# development_board.net
KiCad netlist of a schematic drawn in EAGLE
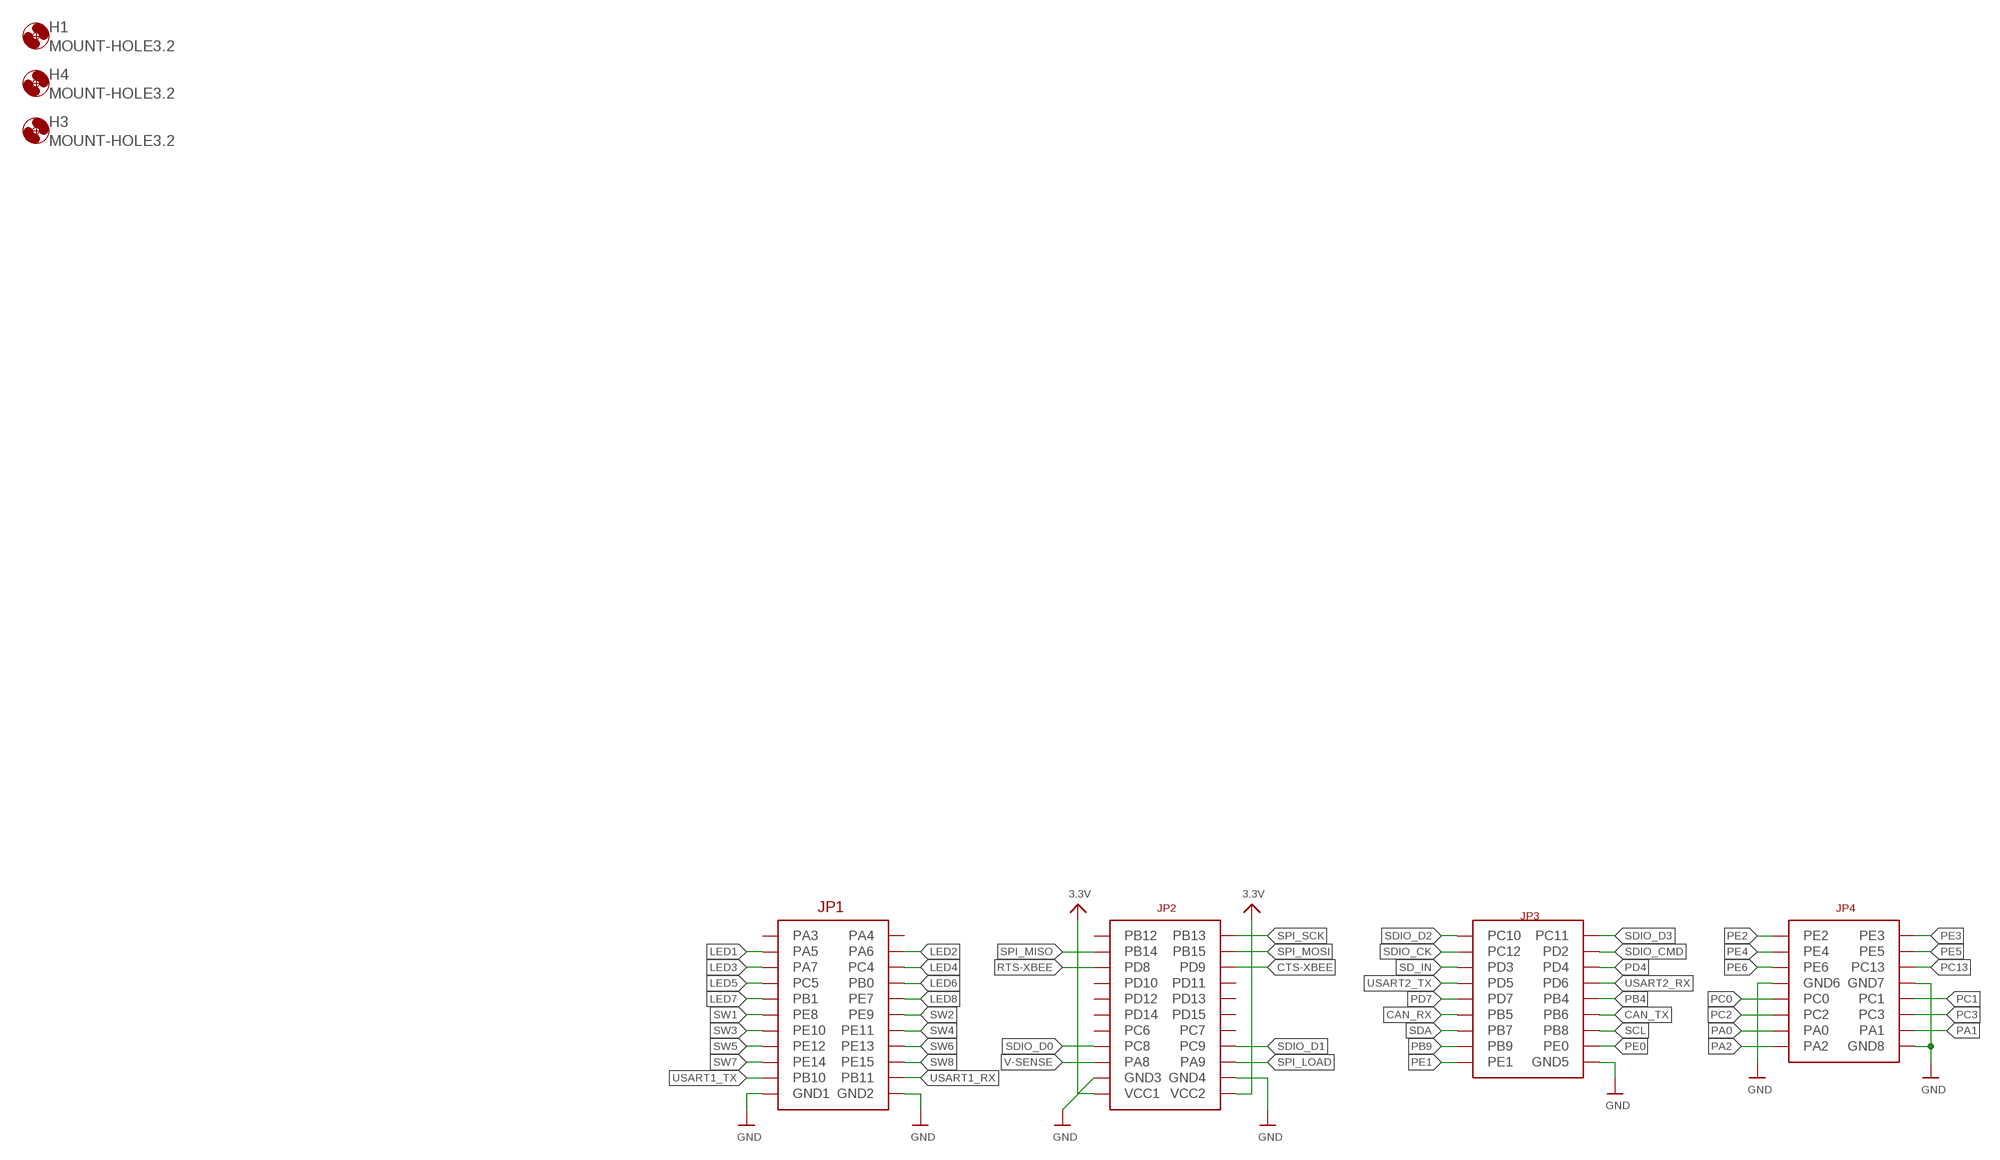
[diagram p0: schematic, sheet 1, part 1 of 3]
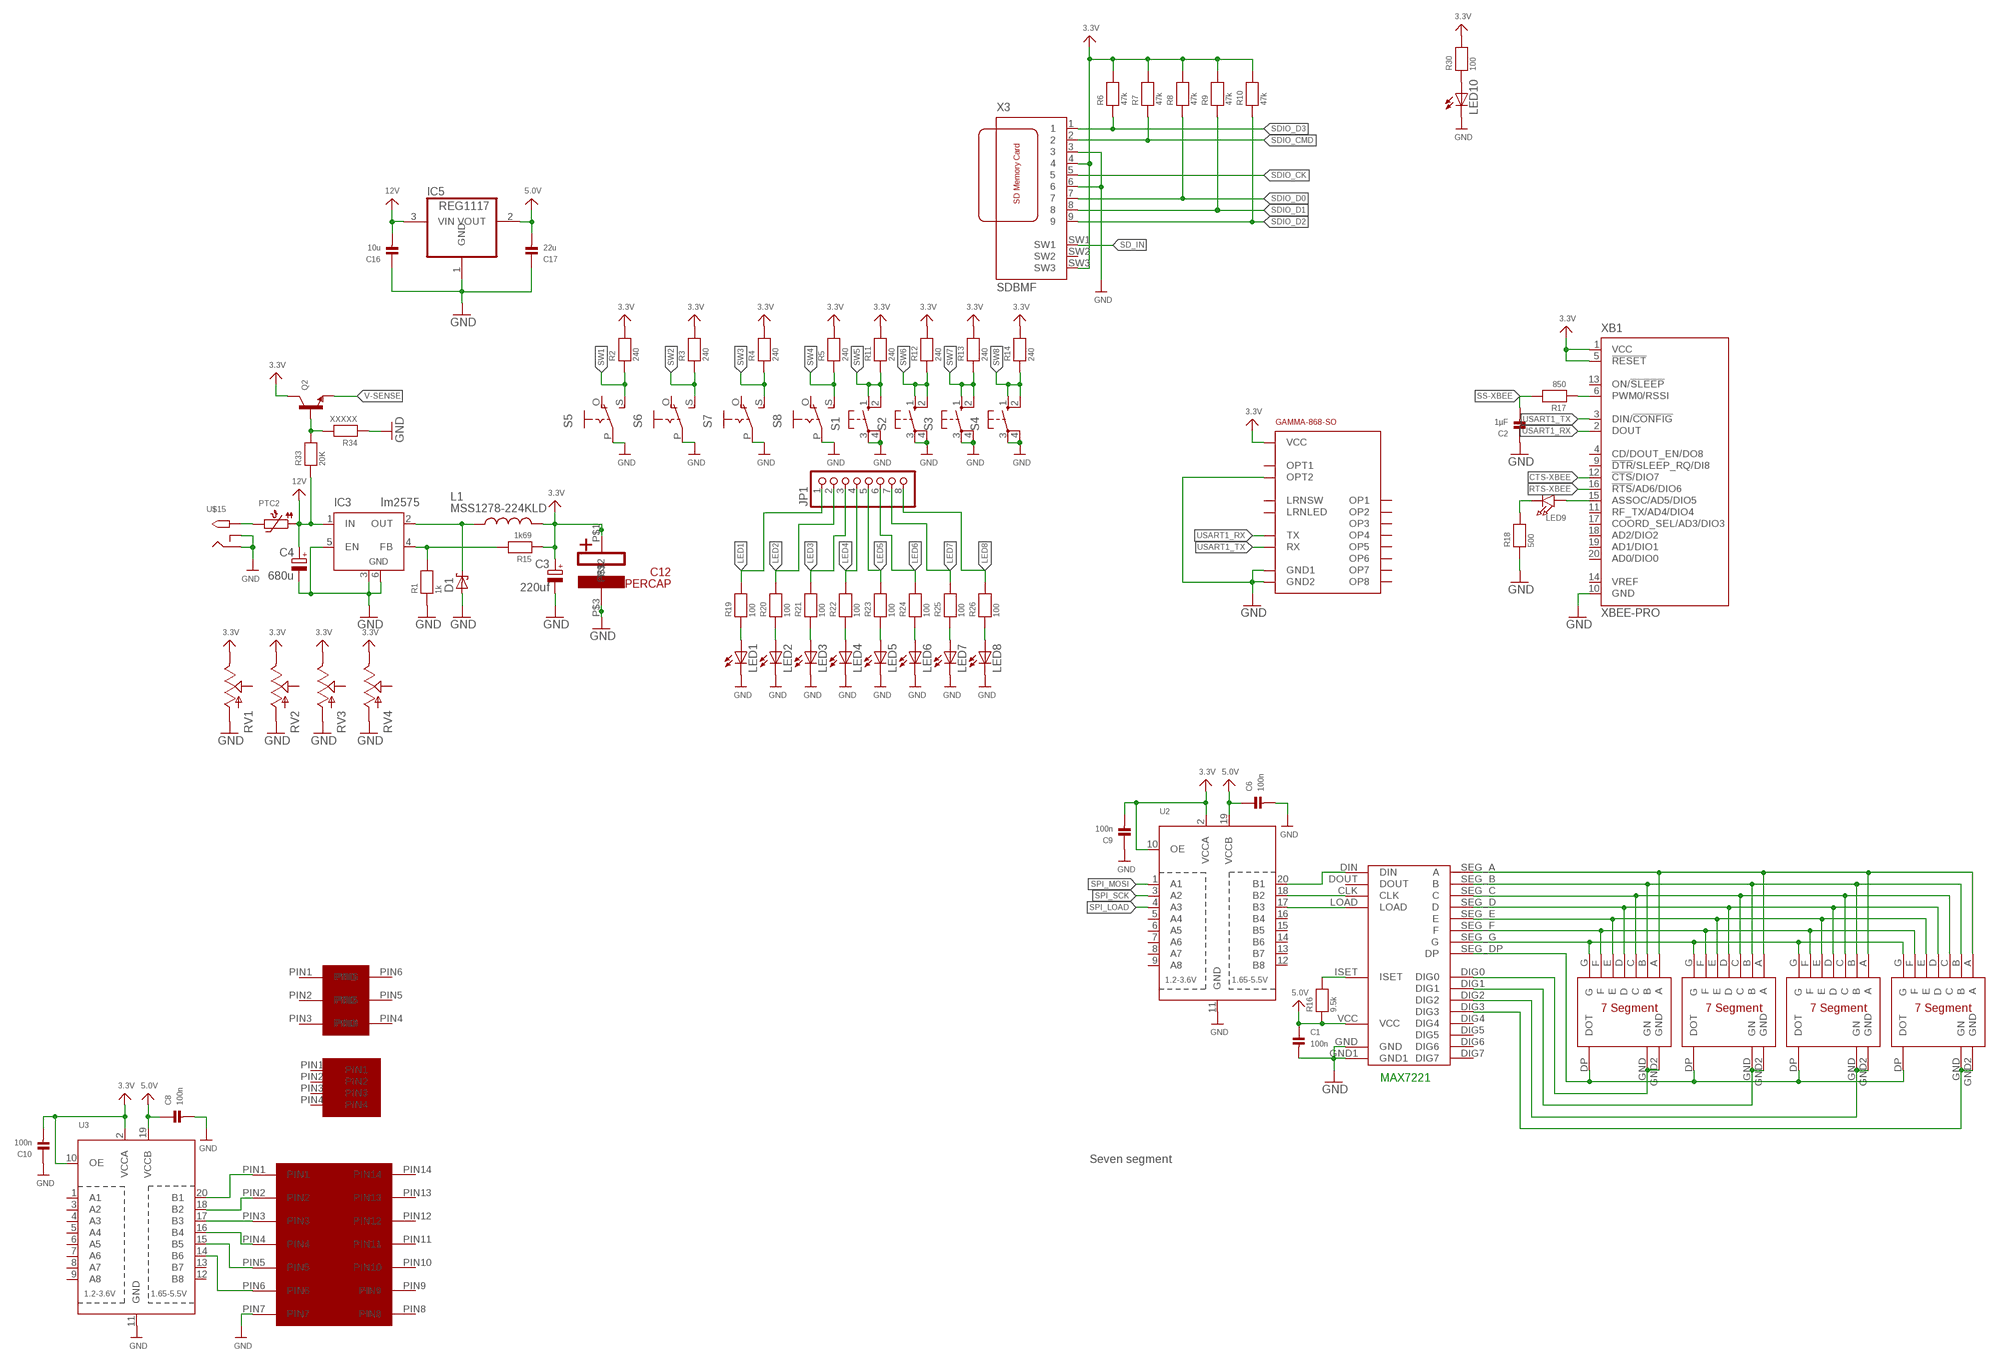
[diagram p1: schematic, sheet 1, part 2 of 3]
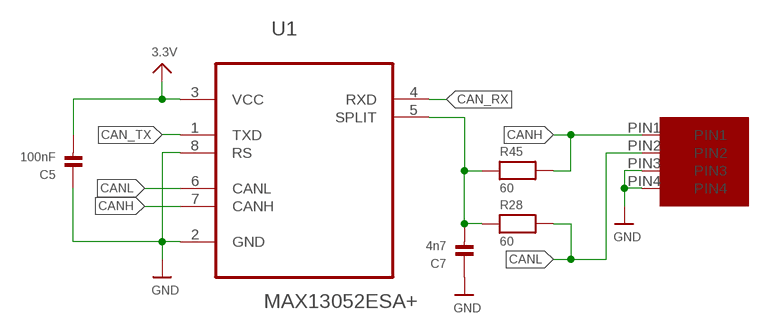
[diagram p2: schematic, sheet 1, part 3 of 3]

(export (version "E")
  (design (tool "Eeschema 10.0.6"))
  (components
    (comp (ref "C1")
      (value "100n")
      (footprint "eagle-import:_0603")
      (libsource (lib "eagle-import") (part "CAP_CERAMIC_0603"))
    )
    (comp (ref "C2")
      (value "1µF")
      (footprint "eagle-import:_0805")
      (libsource (lib "eagle-import") (part "CAP_CERAMIC_0805"))
    )
    (comp (ref "C3")
      (value "220uf")
      (footprint "eagle-import:E3,5-8")
      (libsource (lib "eagle-import") (part "CPOL-EUE3.5-8"))
    )
    (comp (ref "C4")
      (value "680u")
      (footprint "eagle-import:E5-10,5")
      (libsource (lib "eagle-import") (part "CPOL-EUE5-10.5"))
    )
    (comp (ref "C5")
      (value "100nF")
      (footprint "eagle-import:_0603")
      (libsource (lib "eagle-import") (part "CAP_CERAMIC_0603"))
    )
    (comp (ref "C6")
      (value "100n")
      (footprint "eagle-import:_0603")
      (libsource (lib "eagle-import") (part "CAP_CERAMIC_0603"))
    )
    (comp (ref "C7")
      (value "4n7")
      (footprint "eagle-import:_0603")
      (libsource (lib "eagle-import") (part "CAP_CERAMIC_0603"))
    )
    (comp (ref "C8")
      (value "100n")
      (footprint "eagle-import:_0603")
      (libsource (lib "eagle-import") (part "CAP_CERAMIC_0603"))
    )
    (comp (ref "C9")
      (value "100n")
      (footprint "eagle-import:_0603")
      (libsource (lib "eagle-import") (part "CAP_CERAMIC_0603"))
    )
    (comp (ref "C10")
      (value "100n")
      (footprint "eagle-import:_0603")
      (libsource (lib "eagle-import") (part "CAP_CERAMIC_0603"))
    )
    (comp (ref "C12")
      (value "SUPERCAP")
      (footprint "eagle-import:SUPERCAP")
      (libsource (lib "eagle-import") (part "SUPERCAP"))
    )
    (comp (ref "C16")
      (value "10u")
      (footprint "eagle-import:_0805")
      (libsource (lib "eagle-import") (part "CAP_CERAMIC_0805"))
    )
    (comp (ref "C17")
      (value "22u")
      (footprint "eagle-import:_0805")
      (libsource (lib "eagle-import") (part "CAP_CERAMIC_0805"))
    )
    (comp (ref "D1")
      (value "SCHOTTKY-DIODESMC")
      (footprint "eagle-import:SMC")
      (libsource (lib "eagle-import") (part "SCHOTTKY-DIODESMC"))
    )
    (comp (ref "H1")
      (value "MOUNT-HOLE3.2")
      (footprint "eagle-import:3,2")
      (libsource (lib "eagle-import") (part "MOUNT-HOLE3.2"))
    )
    (comp (ref "H3")
      (value "MOUNT-HOLE3.2")
      (footprint "eagle-import:3,2")
      (libsource (lib "eagle-import") (part "MOUNT-HOLE3.2"))
    )
    (comp (ref "H4")
      (value "MOUNT-HOLE3.2")
      (footprint "eagle-import:3,2")
      (libsource (lib "eagle-import") (part "MOUNT-HOLE3.2"))
    )
    (comp (ref "IC3")
      (value "lm2575")
      (footprint "eagle-import:TO263-5")
      (libsource (lib "eagle-import") (part "LM2596S"))
    )
    (comp (ref "IC5")
      (value "REG1117")
      (footprint "eagle-import:SOT223")
      (libsource (lib "eagle-import") (part "REG1117"))
    )
    (comp (ref "JP1")
      (value "PINHD-1X8BIG")
      (footprint "eagle-import:1X08-BIG")
      (libsource (lib "eagle-import") (part "PINHD-1X8BIG"))
    )
    (comp (ref "L1")
      (value "MSS1278-224KLD")
      (footprint "eagle-import:CDRH125")
      (libsource (lib "eagle-import") (part "INDUCTORPWR"))
    )
    (comp (ref "LED1")
      (value "LEDCHIPLED_1206")
      (footprint "eagle-import:CHIPLED_1206")
      (libsource (lib "eagle-import") (part "LEDCHIPLED_1206"))
    )
    (comp (ref "LED2")
      (value "LEDCHIPLED_1206")
      (footprint "eagle-import:CHIPLED_1206")
      (libsource (lib "eagle-import") (part "LEDCHIPLED_1206"))
    )
    (comp (ref "LED3")
      (value "LEDCHIPLED_1206")
      (footprint "eagle-import:CHIPLED_1206")
      (libsource (lib "eagle-import") (part "LEDCHIPLED_1206"))
    )
    (comp (ref "LED4")
      (value "LEDCHIPLED_1206")
      (footprint "eagle-import:CHIPLED_1206")
      (libsource (lib "eagle-import") (part "LEDCHIPLED_1206"))
    )
    (comp (ref "LED5")
      (value "LEDCHIPLED_1206")
      (footprint "eagle-import:CHIPLED_1206")
      (libsource (lib "eagle-import") (part "LEDCHIPLED_1206"))
    )
    (comp (ref "LED6")
      (value "LEDCHIPLED_1206")
      (footprint "eagle-import:CHIPLED_1206")
      (libsource (lib "eagle-import") (part "LEDCHIPLED_1206"))
    )
    (comp (ref "LED7")
      (value "LEDCHIPLED_1206")
      (footprint "eagle-import:CHIPLED_1206")
      (libsource (lib "eagle-import") (part "LEDCHIPLED_1206"))
    )
    (comp (ref "LED8")
      (value "LEDCHIPLED_1206")
      (footprint "eagle-import:CHIPLED_1206")
      (libsource (lib "eagle-import") (part "LEDCHIPLED_1206"))
    )
    (comp (ref "LED9")
      (value "LED1206")
      (footprint "eagle-import:CHIPLED_1206")
      (libsource (lib "eagle-import") (part "LED1206"))
    )
    (comp (ref "LED10")
      (value "LEDCHIPLED_1206")
      (footprint "eagle-import:CHIPLED_1206")
      (libsource (lib "eagle-import") (part "LEDCHIPLED_1206"))
    )
    (comp (ref "MAX7221")
      (value "MAX7221-SMD")
      (footprint "eagle-import:MAX7221")
      (libsource (lib "eagle-import") (part "MAX7221-SMD"))
    )
    (comp (ref "PTC2")
      (value "PTC1812")
      (footprint "eagle-import:PTC1812")
      (libsource (lib "eagle-import") (part "PTC1812"))
    )
    (comp (ref "Q2")
      (value "TRANSISTOR_NPNWIDE")
      (footprint "eagle-import:SOT23-WIDE")
      (libsource (lib "eagle-import") (part "TRANSISTOR_NPNWIDE"))
    )
    (comp (ref "R1")
      (value "1k")
      (footprint "eagle-import:_0603")
      (libsource (lib "eagle-import") (part "RESISTOR_0603"))
    )
    (comp (ref "R2")
      (value "240")
      (footprint "eagle-import:_0603")
      (libsource (lib "eagle-import") (part "RESISTOR_0603"))
    )
    (comp (ref "R3")
      (value "240")
      (footprint "eagle-import:_0603")
      (libsource (lib "eagle-import") (part "RESISTOR_0603"))
    )
    (comp (ref "R4")
      (value "240")
      (footprint "eagle-import:_0603")
      (libsource (lib "eagle-import") (part "RESISTOR_0603"))
    )
    (comp (ref "R5")
      (value "240")
      (footprint "eagle-import:_0603")
      (libsource (lib "eagle-import") (part "RESISTOR_0603"))
    )
    (comp (ref "R6")
      (value "47k")
      (footprint "eagle-import:_0603")
      (libsource (lib "eagle-import") (part "RESISTOR_0603"))
    )
    (comp (ref "R7")
      (value "47k")
      (footprint "eagle-import:_0603")
      (libsource (lib "eagle-import") (part "RESISTOR_0603"))
    )
    (comp (ref "R8")
      (value "47k")
      (footprint "eagle-import:_0603")
      (libsource (lib "eagle-import") (part "RESISTOR_0603"))
    )
    (comp (ref "R9")
      (value "47k")
      (footprint "eagle-import:_0603")
      (libsource (lib "eagle-import") (part "RESISTOR_0603"))
    )
    (comp (ref "R10")
      (value "47k")
      (footprint "eagle-import:_0603")
      (libsource (lib "eagle-import") (part "RESISTOR_0603"))
    )
    (comp (ref "R11")
      (value "240")
      (footprint "eagle-import:_0603")
      (libsource (lib "eagle-import") (part "RESISTOR_0603"))
    )
    (comp (ref "R12")
      (value "240")
      (footprint "eagle-import:_0603")
      (libsource (lib "eagle-import") (part "RESISTOR_0603"))
    )
    (comp (ref "R13")
      (value "240")
      (footprint "eagle-import:_0603")
      (libsource (lib "eagle-import") (part "RESISTOR_0603"))
    )
    (comp (ref "R14")
      (value "240")
      (footprint "eagle-import:_0603")
      (libsource (lib "eagle-import") (part "RESISTOR_0603"))
    )
    (comp (ref "R15")
      (value "1k69")
      (footprint "eagle-import:_0603")
      (libsource (lib "eagle-import") (part "RESISTOR_0603"))
    )
    (comp (ref "R16")
      (value "9.5k")
      (footprint "eagle-import:_0603")
      (libsource (lib "eagle-import") (part "RESISTOR_0603"))
    )
    (comp (ref "R17")
      (value "850")
      (footprint "eagle-import:_0603")
      (libsource (lib "eagle-import") (part "RESISTOR_0603"))
    )
    (comp (ref "R18")
      (value "500")
      (footprint "eagle-import:_0603")
      (libsource (lib "eagle-import") (part "RESISTOR_0603"))
    )
    (comp (ref "R19")
      (value "100")
      (footprint "eagle-import:_0603")
      (libsource (lib "eagle-import") (part "RESISTOR_0603"))
    )
    (comp (ref "R20")
      (value "100")
      (footprint "eagle-import:_0603")
      (libsource (lib "eagle-import") (part "RESISTOR_0603"))
    )
    (comp (ref "R21")
      (value "100")
      (footprint "eagle-import:_0603")
      (libsource (lib "eagle-import") (part "RESISTOR_0603"))
    )
    (comp (ref "R22")
      (value "100")
      (footprint "eagle-import:_0603")
      (libsource (lib "eagle-import") (part "RESISTOR_0603"))
    )
    (comp (ref "R23")
      (value "100")
      (footprint "eagle-import:_0603")
      (libsource (lib "eagle-import") (part "RESISTOR_0603"))
    )
    (comp (ref "R24")
      (value "100")
      (footprint "eagle-import:_0603")
      (libsource (lib "eagle-import") (part "RESISTOR_0603"))
    )
    (comp (ref "R25")
      (value "100")
      (footprint "eagle-import:_0603")
      (libsource (lib "eagle-import") (part "RESISTOR_0603"))
    )
    (comp (ref "R26")
      (value "100")
      (footprint "eagle-import:_0603")
      (libsource (lib "eagle-import") (part "RESISTOR_0603"))
    )
    (comp (ref "R28")
      (value "60")
      (footprint "eagle-import:_0603")
      (libsource (lib "eagle-import") (part "RESISTOR_0603"))
    )
    (comp (ref "R30")
      (value "100")
      (footprint "eagle-import:_0603")
      (libsource (lib "eagle-import") (part "RESISTOR_0603"))
    )
    (comp (ref "R33")
      (value "20K")
      (footprint "eagle-import:_0603")
      (libsource (lib "eagle-import") (part "RESISTOR_0603"))
    )
    (comp (ref "R34")
      (value "XXXXX")
      (footprint "eagle-import:_0603")
      (libsource (lib "eagle-import") (part "RESISTOR_0603"))
    )
    (comp (ref "R45")
      (value "60")
      (footprint "eagle-import:_0603")
      (libsource (lib "eagle-import") (part "RESISTOR_0603"))
    )
    (comp (ref "RV1")
      (value "POT")
      (footprint "eagle-import:ALPS_POT")
      (libsource (lib "eagle-import") (part "POT"))
    )
    (comp (ref "RV2")
      (value "POT")
      (footprint "eagle-import:ALPS_POT")
      (libsource (lib "eagle-import") (part "POT"))
    )
    (comp (ref "RV3")
      (value "POT")
      (footprint "eagle-import:ALPS_POT")
      (libsource (lib "eagle-import") (part "POT"))
    )
    (comp (ref "RV4")
      (value "POT")
      (footprint "eagle-import:ALPS_POT")
      (libsource (lib "eagle-import") (part "POT"))
    )
    (comp (ref "S1")
      (value "10-XX")
      (footprint "eagle-import:B3F-10XX")
      (fields
        (field (name "MPN") "B3F-1000")
        (field (name "MPN_1") "B3F-1000")
        (field (name "OC_FARNELL") "176432")
        (field (name "OC_NEWARK") "36M3542")
      )
      (libsource (lib "eagle-import") (part "10-XX"))
    )
    (comp (ref "S2")
      (value "10-XX")
      (footprint "eagle-import:B3F-10XX")
      (fields
        (field (name "MPN") "B3F-1000")
        (field (name "MPN_1") "B3F-1000")
        (field (name "OC_FARNELL") "176432")
        (field (name "OC_NEWARK") "36M3542")
      )
      (libsource (lib "eagle-import") (part "10-XX"))
    )
    (comp (ref "S3")
      (value "10-XX")
      (footprint "eagle-import:B3F-10XX")
      (fields
        (field (name "MPN") "B3F-1000")
        (field (name "MPN_1") "B3F-1000")
        (field (name "OC_FARNELL") "176432")
        (field (name "OC_NEWARK") "36M3542")
      )
      (libsource (lib "eagle-import") (part "10-XX"))
    )
    (comp (ref "S4")
      (value "10-XX")
      (footprint "eagle-import:B3F-10XX")
      (fields
        (field (name "MPN") "B3F-1000")
        (field (name "MPN_1") "B3F-1000")
        (field (name "OC_FARNELL") "176432")
        (field (name "OC_NEWARK") "36M3542")
      )
      (libsource (lib "eagle-import") (part "10-XX"))
    )
    (comp (ref "S5")
      (value "EG1218S")
      (footprint "eagle-import:EG1218")
      (libsource (lib "eagle-import") (part "EG1218S"))
    )
    (comp (ref "S6")
      (value "EG1218S")
      (footprint "eagle-import:EG1218")
      (libsource (lib "eagle-import") (part "EG1218S"))
    )
    (comp (ref "S7")
      (value "EG1218S")
      (footprint "eagle-import:EG1218")
      (libsource (lib "eagle-import") (part "EG1218S"))
    )
    (comp (ref "S8")
      (value "EG1218S")
      (footprint "eagle-import:EG1218")
      (libsource (lib "eagle-import") (part "EG1218S"))
    )
    (comp (ref "U$1")
      (value "CPU-BOARD")
      (footprint "eagle-import:CPU-BOARD-JP1")
      (libsource (lib "eagle-import") (part "CPU-BOARD"))
    )
    (comp (ref "U$2")
      (value "GAMMA-868-SO")
      (footprint "eagle-import:UNICORN_V2_GAMMA-868-SO")
      (libsource (lib "eagle-import") (part "GAMMA-868-SO"))
    )
    (comp (ref "U$15")
      (value "2.1MMJACKSMT")
      (footprint "eagle-import:DCJACK_2MM_SMT")
      (libsource (lib "eagle-import") (part "2.1MMJACKSMT"))
    )
    (comp (ref "U$23")
      (value "REDSEVENSEGMENT")
      (footprint "eagle-import:REDSEGMENT")
      (libsource (lib "eagle-import") (part "REDSEVENSEGMENT"))
    )
    (comp (ref "U$24")
      (value "REDSEVENSEGMENT")
      (footprint "eagle-import:REDSEGMENT")
      (libsource (lib "eagle-import") (part "REDSEVENSEGMENT"))
    )
    (comp (ref "U$25")
      (value "REDSEVENSEGMENT")
      (footprint "eagle-import:REDSEGMENT")
      (libsource (lib "eagle-import") (part "REDSEVENSEGMENT"))
    )
    (comp (ref "U$26")
      (value "REDSEVENSEGMENT")
      (footprint "eagle-import:REDSEGMENT")
      (libsource (lib "eagle-import") (part "REDSEVENSEGMENT"))
    )
    (comp (ref "U$57")
      (value "MICROFIT4")
      (footprint "eagle-import:MICROFIT4SOCK")
      (libsource (lib "eagle-import") (part "MICROFIT4"))
    )
    (comp (ref "U$61")
      (value "MICROFIT14")
      (footprint "eagle-import:MICROFIT14SOCK")
      (libsource (lib "eagle-import") (part "MICROFIT14"))
    )
    (comp (ref "U$67")
      (value "MICROFIT4")
      (footprint "eagle-import:MICROFIT4SOCK")
      (libsource (lib "eagle-import") (part "MICROFIT4"))
    )
    (comp (ref "U$68")
      (value "MICROFIT6")
      (footprint "eagle-import:MICROFIT6SOCK")
      (libsource (lib "eagle-import") (part "MICROFIT6"))
    )
    (comp (ref "U1")
      (value "MAX13052ESA+")
      (footprint "eagle-import:SOIC127P600X175-8N")
      (libsource (lib "eagle-import") (part "MAX13052ESA+"))
    )
    (comp (ref "U2")
      (value "TXB0108PWR")
      (footprint "eagle-import:TSSOP20")
      (libsource (lib "eagle-import") (part "TXB0108PWR"))
    )
    (comp (ref "U3")
      (value "TXB0108PWR")
      (footprint "eagle-import:TSSOP20")
      (libsource (lib "eagle-import") (part "TXB0108PWR"))
    )
    (comp (ref "X3")
      (value "SDBMF")
      (footprint "eagle-import:SDBMF-009XXBXX2")
      (libsource (lib "eagle-import") (part "SDBMF"))
    )
    (comp (ref "XB1")
      (value "XBEE-PRO")
      (footprint "eagle-import:XBEE-PRO")
      (fields (field (name "MPN") "XBP24-AWI-001"))
      (libsource (lib "eagle-import") (part "XBEE-PRO"))
    )
  )
  (nets
    (net (code "1") (name "3.3V") (class "Default")
      (node (ref "C10") (pin "2") (pinfunction "P$2_2") (pintype "passive"))
      (node (ref "C12") (pin "P$1") (pinfunction "P$1_P$1") (pintype "bidirectional"))
      (node (ref "C3") (pin "+") (pinfunction "+_+") (pintype "passive"))
      (node (ref "C5") (pin "2") (pinfunction "P$2_2") (pintype "passive"))
      (node (ref "C9") (pin "2") (pinfunction "P$2_2") (pintype "passive"))
      (node (ref "L1") (pin "2") (pinfunction "2_2") (pintype "passive"))
      (node (ref "Q2") (pin "3") (pinfunction "C_3") (pintype "passive"))
      (node (ref "R10") (pin "2") (pinfunction "2_2") (pintype "passive"))
      (node (ref "R11") (pin "2") (pinfunction "2_2") (pintype "passive"))
      (node (ref "R12") (pin "2") (pinfunction "2_2") (pintype "passive"))
      (node (ref "R13") (pin "2") (pinfunction "2_2") (pintype "passive"))
      (node (ref "R14") (pin "2") (pinfunction "2_2") (pintype "passive"))
      (node (ref "R15") (pin "1") (pinfunction "1_1") (pintype "passive"))
      (node (ref "R2") (pin "2") (pinfunction "2_2") (pintype "passive"))
      (node (ref "R3") (pin "2") (pinfunction "2_2") (pintype "passive"))
      (node (ref "R30") (pin "2") (pinfunction "2_2") (pintype "passive"))
      (node (ref "R4") (pin "2") (pinfunction "2_2") (pintype "passive"))
      (node (ref "R5") (pin "2") (pinfunction "2_2") (pintype "passive"))
      (node (ref "R6") (pin "2") (pinfunction "2_2") (pintype "passive"))
      (node (ref "R7") (pin "2") (pinfunction "2_2") (pintype "passive"))
      (node (ref "R8") (pin "2") (pinfunction "2_2") (pintype "passive"))
      (node (ref "R9") (pin "2") (pinfunction "2_2") (pintype "passive"))
      (node (ref "RV1") (pin "P$1") (pinfunction "E_P$1") (pintype "passive"))
      (node (ref "RV2") (pin "P$1") (pinfunction "E_P$1") (pintype "passive"))
      (node (ref "RV3") (pin "P$1") (pinfunction "E_P$1") (pintype "passive"))
      (node (ref "RV4") (pin "P$1") (pinfunction "E_P$1") (pintype "passive"))
      (node (ref "U$1") (pin "P$43") (pinfunction "VCC1_P$43") (pintype "bidirectional"))
      (node (ref "U$1") (pin "P$44") (pinfunction "VCC2_P$44") (pintype "bidirectional"))
      (node (ref "U$2") (pin "P$16") (pinfunction "VCC_P$16") (pintype "bidirectional"))
      (node (ref "U1") (pin "3") (pinfunction "VCC_3") (pintype "power_in"))
      (node (ref "U2") (pin "10") (pinfunction "OE_10") (pintype "bidirectional"))
      (node (ref "U2") (pin "2") (pinfunction "VCCA_2") (pintype "bidirectional"))
      (node (ref "U3") (pin "10") (pinfunction "OE_10") (pintype "bidirectional"))
      (node (ref "U3") (pin "2") (pinfunction "VCCA_2") (pintype "bidirectional"))
      (node (ref "X3") (pin "4") (pinfunction "4_4") (pintype "passive"))
      (node (ref "X3") (pin "SW3") (pinfunction "SW3_SW3") (pintype "passive"))
      (node (ref "XB1") (pin "1") (pinfunction "VCC_1") (pintype "power_in"))
      (node (ref "XB1") (pin "5") (pinfunction "~{RESET}_5") (pintype "input"))
    )
    (net (code "2") (name "5.0V") (class "Default")
      (node (ref "C1") (pin "1") (pinfunction "P$1_1") (pintype "passive"))
      (node (ref "C17") (pin "2") (pinfunction "P$2_2") (pintype "passive"))
      (node (ref "C6") (pin "1") (pinfunction "P$1_1") (pintype "passive"))
      (node (ref "C8") (pin "1") (pinfunction "P$1_1") (pintype "passive"))
      (node (ref "IC5") (pin "2") (pinfunction "VOUT_2") (pintype "output"))
      (node (ref "MAX7221") (pin "VCC") (pinfunction "VCC_VCC") (pintype "bidirectional"))
      (node (ref "R16") (pin "1") (pinfunction "1_1") (pintype "passive"))
      (node (ref "U2") (pin "19") (pinfunction "VCCB_19") (pintype "bidirectional"))
      (node (ref "U3") (pin "19") (pinfunction "VCCB_19") (pintype "bidirectional"))
    )
    (net (code "3") (name "12V") (class "Default")
      (node (ref "C16") (pin "2") (pinfunction "P$2_2") (pintype "passive"))
      (node (ref "C4") (pin "+") (pinfunction "+_+") (pintype "passive"))
      (node (ref "IC3") (pin "1") (pinfunction "IN_1") (pintype "input"))
      (node (ref "IC5") (pin "3") (pinfunction "VIN_3") (pintype "input"))
      (node (ref "PTC2") (pin "P$1") (pinfunction "1_P$1") (pintype "passive"))
      (node (ref "R33") (pin "1") (pinfunction "1_1") (pintype "passive"))
    )
    (net (code "4") (name "CANH") (class "Default")
      (node (ref "R45") (pin "2") (pinfunction "2_2") (pintype "passive"))
      (node (ref "U$57") (pin "PIN1") (pinfunction "PIN1_PIN1") (pintype "bidirectional"))
      (node (ref "U1") (pin "7") (pinfunction "CANH_7") (pintype "input"))
    )
    (net (code "5") (name "CANL") (class "Default")
      (node (ref "R28") (pin "2") (pinfunction "2_2") (pintype "passive"))
      (node (ref "U$57") (pin "PIN2") (pinfunction "PIN2_PIN2") (pintype "bidirectional"))
      (node (ref "U1") (pin "6") (pinfunction "CANL_6") (pintype "input"))
    )
    (net (code "6") (name "CAN_RX") (class "Default")
      (node (ref "U$1") (pin "P$55") (pinfunction "PB5_P$55") (pintype "bidirectional"))
      (node (ref "U1") (pin "4") (pinfunction "RXD_4") (pintype "output"))
    )
    (net (code "7") (name "CAN_TX") (class "Default")
      (node (ref "U$1") (pin "P$56") (pinfunction "PB6_P$56") (pintype "bidirectional"))
      (node (ref "U1") (pin "1") (pinfunction "TXD_1") (pintype "input"))
    )
    (net (code "8") (name "CTS-XBEE") (class "Default")
      (node (ref "U$1") (pin "P$28") (pinfunction "PD9_P$28") (pintype "bidirectional"))
      (node (ref "XB1") (pin "12") (pinfunction "~{CTS}/DIO7_12") (pintype "bidirectional"))
    )
    (net (code "9") (name "GND") (class "Default")
      (node (ref "C1") (pin "2") (pinfunction "P$2_2") (pintype "passive"))
      (node (ref "C10") (pin "1") (pinfunction "P$1_1") (pintype "passive"))
      (node (ref "C12") (pin "P$3") (pinfunction "P$2_P$3") (pintype "bidirectional"))
      (node (ref "C16") (pin "1") (pinfunction "P$1_1") (pintype "passive"))
      (node (ref "C17") (pin "1") (pinfunction "P$1_1") (pintype "passive"))
      (node (ref "C2") (pin "1") (pinfunction "P$1_1") (pintype "passive"))
      (node (ref "C3") (pin "-") (pinfunction "-_-") (pintype "passive"))
      (node (ref "C4") (pin "-") (pinfunction "-_-") (pintype "passive"))
      (node (ref "C5") (pin "1") (pinfunction "P$1_1") (pintype "passive"))
      (node (ref "C6") (pin "2") (pinfunction "P$2_2") (pintype "passive"))
      (node (ref "C7") (pin "1") (pinfunction "P$1_1") (pintype "passive"))
      (node (ref "C8") (pin "2") (pinfunction "P$2_2") (pintype "passive"))
      (node (ref "C9") (pin "1") (pinfunction "P$1_1") (pintype "passive"))
      (node (ref "D1") (pin "A") (pinfunction "A_A") (pintype "passive"))
      (node (ref "IC3") (pin "3") (pinfunction "GND_3") (pintype "power_in"))
      (node (ref "IC3") (pin "5") (pinfunction "EN_5") (pintype "input"))
      (node (ref "IC3") (pin "6") (pinfunction "GND_6") (pintype "power_in"))
      (node (ref "IC5") (pin "1") (pinfunction "GND_1") (pintype "power_in"))
      (node (ref "LED1") (pin "C") (pinfunction "C_C") (pintype "passive"))
      (node (ref "LED10") (pin "C") (pinfunction "C_C") (pintype "passive"))
      (node (ref "LED2") (pin "C") (pinfunction "C_C") (pintype "passive"))
      (node (ref "LED3") (pin "C") (pinfunction "C_C") (pintype "passive"))
      (node (ref "LED4") (pin "C") (pinfunction "C_C") (pintype "passive"))
      (node (ref "LED5") (pin "C") (pinfunction "C_C") (pintype "passive"))
      (node (ref "LED6") (pin "C") (pinfunction "C_C") (pintype "passive"))
      (node (ref "LED7") (pin "C") (pinfunction "C_C") (pintype "passive"))
      (node (ref "LED8") (pin "C") (pinfunction "C_C") (pintype "passive"))
      (node (ref "MAX7221") (pin "GND") (pinfunction "GND_GND") (pintype "bidirectional"))
      (node (ref "MAX7221") (pin "GND1") (pinfunction "GND1_GND1") (pintype "bidirectional"))
      (node (ref "R1") (pin "1") (pinfunction "1_1") (pintype "passive"))
      (node (ref "R18") (pin "1") (pinfunction "1_1") (pintype "passive"))
      (node (ref "R34") (pin "1") (pinfunction "1_1") (pintype "passive"))
      (node (ref "RV1") (pin "P$3") (pinfunction "A_P$3") (pintype "passive"))
      (node (ref "RV2") (pin "P$3") (pinfunction "A_P$3") (pintype "passive"))
      (node (ref "RV3") (pin "P$3") (pinfunction "A_P$3") (pintype "passive"))
      (node (ref "RV4") (pin "P$3") (pinfunction "A_P$3") (pintype "passive"))
      (node (ref "S1") (pin "3") (pinfunction "P_3") (pintype "passive"))
      (node (ref "S1") (pin "4") (pinfunction "P1_4") (pintype "passive"))
      (node (ref "S2") (pin "3") (pinfunction "P_3") (pintype "passive"))
      (node (ref "S2") (pin "4") (pinfunction "P1_4") (pintype "passive"))
      (node (ref "S3") (pin "3") (pinfunction "P_3") (pintype "passive"))
      (node (ref "S3") (pin "4") (pinfunction "P1_4") (pintype "passive"))
      (node (ref "S4") (pin "3") (pinfunction "P_3") (pintype "passive"))
      (node (ref "S4") (pin "4") (pinfunction "P1_4") (pintype "passive"))
      (node (ref "S5") (pin "P") (pinfunction "P_P") (pintype "passive"))
      (node (ref "S6") (pin "P") (pinfunction "P_P") (pintype "passive"))
      (node (ref "S7") (pin "P") (pinfunction "P_P") (pintype "passive"))
      (node (ref "S8") (pin "P") (pinfunction "P_P") (pintype "passive"))
      (node (ref "U$1") (pin "P$19") (pinfunction "GND1_P$19") (pintype "bidirectional"))
      (node (ref "U$1") (pin "P$20") (pinfunction "GND2_P$20") (pintype "bidirectional"))
      (node (ref "U$1") (pin "P$41") (pinfunction "GND3_P$41") (pintype "bidirectional"))
      (node (ref "U$1") (pin "P$42") (pinfunction "GND4_P$42") (pintype "bidirectional"))
      (node (ref "U$1") (pin "P$62") (pinfunction "GND5_P$62") (pintype "bidirectional"))
      (node (ref "U$1") (pin "P$69") (pinfunction "GND6_P$69") (pintype "bidirectional"))
      (node (ref "U$1") (pin "P$70") (pinfunction "GND7_P$70") (pintype "bidirectional"))
      (node (ref "U$1") (pin "P$78") (pinfunction "GND8_P$78") (pintype "bidirectional"))
      (node (ref "U$15") (pin "GND") (pinfunction "RING_GND") (pintype "bidirectional"))
      (node (ref "U$15") (pin "GNDBREAK") (pinfunction "RING_SW_GNDBREAK") (pintype "bidirectional"))
      (node (ref "U$2") (pin "P$14") (pinfunction "OPT2_P$14") (pintype "bidirectional"))
      (node (ref "U$2") (pin "P$15") (pinfunction "GND2_P$15") (pintype "bidirectional"))
      (node (ref "U$2") (pin "P$2") (pinfunction "GND1_P$2") (pintype "bidirectional"))
      (node (ref "U$57") (pin "PIN3") (pinfunction "PIN3_PIN3") (pintype "bidirectional"))
      (node (ref "U$57") (pin "PIN4") (pinfunction "PIN4_PIN4") (pintype "bidirectional"))
      (node (ref "U$61") (pin "PIN7") (pinfunction "PIN7_PIN7") (pintype "bidirectional"))
      (node (ref "U1") (pin "2") (pinfunction "GND_2") (pintype "passive"))
      (node (ref "U1") (pin "8") (pinfunction "RS_8") (pintype "input"))
      (node (ref "U2") (pin "11") (pinfunction "GND_11") (pintype "bidirectional"))
      (node (ref "U3") (pin "11") (pinfunction "GND_11") (pintype "bidirectional"))
      (node (ref "X3") (pin "3") (pinfunction "3_3") (pintype "passive"))
      (node (ref "X3") (pin "6") (pinfunction "6_6") (pintype "passive"))
      (node (ref "XB1") (pin "10") (pinfunction "GND_10") (pintype "power_in"))
    )
    (net (code "10") (name "LED1") (class "Default")
      (node (ref "JP1") (pin "1") (pinfunction "1_1") (pintype "passive"))
      (node (ref "R19") (pin "2") (pinfunction "2_2") (pintype "passive"))
      (node (ref "U$1") (pin "P$3") (pinfunction "PA5_P$3") (pintype "bidirectional"))
    )
    (net (code "11") (name "LED2") (class "Default")
      (node (ref "JP1") (pin "2") (pinfunction "2_2") (pintype "passive"))
      (node (ref "R20") (pin "2") (pinfunction "2_2") (pintype "passive"))
      (node (ref "U$1") (pin "P$4") (pinfunction "PA6_P$4") (pintype "bidirectional"))
    )
    (net (code "12") (name "LED3") (class "Default")
      (node (ref "JP1") (pin "3") (pinfunction "3_3") (pintype "passive"))
      (node (ref "R21") (pin "2") (pinfunction "2_2") (pintype "passive"))
      (node (ref "U$1") (pin "P$5") (pinfunction "PA7_P$5") (pintype "bidirectional"))
    )
    (net (code "13") (name "LED4") (class "Default")
      (node (ref "JP1") (pin "4") (pinfunction "4_4") (pintype "passive"))
      (node (ref "R22") (pin "2") (pinfunction "2_2") (pintype "passive"))
      (node (ref "U$1") (pin "P$6") (pinfunction "PC4_P$6") (pintype "bidirectional"))
    )
    (net (code "14") (name "LED5") (class "Default")
      (node (ref "JP1") (pin "5") (pinfunction "5_5") (pintype "passive"))
      (node (ref "R23") (pin "2") (pinfunction "2_2") (pintype "passive"))
      (node (ref "U$1") (pin "P$7") (pinfunction "PC5_P$7") (pintype "bidirectional"))
    )
    (net (code "15") (name "LED6") (class "Default")
      (node (ref "JP1") (pin "6") (pinfunction "6_6") (pintype "passive"))
      (node (ref "R24") (pin "2") (pinfunction "2_2") (pintype "passive"))
      (node (ref "U$1") (pin "P$8") (pinfunction "PB0_P$8") (pintype "bidirectional"))
    )
    (net (code "16") (name "LED7") (class "Default")
      (node (ref "JP1") (pin "7") (pinfunction "7_7") (pintype "passive"))
      (node (ref "R25") (pin "2") (pinfunction "2_2") (pintype "passive"))
      (node (ref "U$1") (pin "P$9") (pinfunction "PB1_P$9") (pintype "bidirectional"))
    )
    (net (code "17") (name "LED8") (class "Default")
      (node (ref "JP1") (pin "8") (pinfunction "8_8") (pintype "passive"))
      (node (ref "R26") (pin "2") (pinfunction "2_2") (pintype "passive"))
      (node (ref "U$1") (pin "P$10") (pinfunction "PE7_P$10") (pintype "bidirectional"))
    )
    (net (code "18") (name "Net-(C7-P$2)") (class "Default")
      (node (ref "C7") (pin "2") (pinfunction "P$2_2") (pintype "passive"))
      (node (ref "R28") (pin "1") (pinfunction "1_1") (pintype "passive"))
      (node (ref "R45") (pin "1") (pinfunction "1_1") (pintype "passive"))
      (node (ref "U1") (pin "5") (pinfunction "SPLIT_5") (pintype "output"))
    )
    (net (code "19") (name "Net-(IC3-FB)") (class "Default")
      (node (ref "IC3") (pin "4") (pinfunction "FB_4") (pintype "input"))
      (node (ref "R1") (pin "2") (pinfunction "2_2") (pintype "passive"))
      (node (ref "R15") (pin "2") (pinfunction "2_2") (pintype "passive"))
    )
    (net (code "20") (name "Net-(IC3-OUT)") (class "Default")
      (node (ref "D1") (pin "C") (pinfunction "C_C") (pintype "passive"))
      (node (ref "IC3") (pin "2") (pinfunction "OUT_2") (pintype "output"))
      (node (ref "L1") (pin "1") (pinfunction "1_1") (pintype "passive"))
    )
    (net (code "21") (name "Net-(LED1-PadA)") (class "Default")
      (node (ref "LED1") (pin "A") (pinfunction "A_A") (pintype "passive"))
      (node (ref "R19") (pin "1") (pinfunction "1_1") (pintype "passive"))
    )
    (net (code "22") (name "Net-(LED2-PadA)") (class "Default")
      (node (ref "LED2") (pin "A") (pinfunction "A_A") (pintype "passive"))
      (node (ref "R20") (pin "1") (pinfunction "1_1") (pintype "passive"))
    )
    (net (code "23") (name "Net-(LED3-PadA)") (class "Default")
      (node (ref "LED3") (pin "A") (pinfunction "A_A") (pintype "passive"))
      (node (ref "R21") (pin "1") (pinfunction "1_1") (pintype "passive"))
    )
    (net (code "24") (name "Net-(LED4-PadA)") (class "Default")
      (node (ref "LED4") (pin "A") (pinfunction "A_A") (pintype "passive"))
      (node (ref "R22") (pin "1") (pinfunction "1_1") (pintype "passive"))
    )
    (net (code "25") (name "Net-(LED5-PadA)") (class "Default")
      (node (ref "LED5") (pin "A") (pinfunction "A_A") (pintype "passive"))
      (node (ref "R23") (pin "1") (pinfunction "1_1") (pintype "passive"))
    )
    (net (code "26") (name "Net-(LED6-PadA)") (class "Default")
      (node (ref "LED6") (pin "A") (pinfunction "A_A") (pintype "passive"))
      (node (ref "R24") (pin "1") (pinfunction "1_1") (pintype "passive"))
    )
    (net (code "27") (name "Net-(LED7-PadA)") (class "Default")
      (node (ref "LED7") (pin "A") (pinfunction "A_A") (pintype "passive"))
      (node (ref "R25") (pin "1") (pinfunction "1_1") (pintype "passive"))
    )
    (net (code "28") (name "Net-(LED8-PadA)") (class "Default")
      (node (ref "LED8") (pin "A") (pinfunction "A_A") (pintype "passive"))
      (node (ref "R26") (pin "1") (pinfunction "1_1") (pintype "passive"))
    )
    (net (code "29") (name "Net-(LED9-PadC)") (class "Default")
      (node (ref "LED9") (pin "C") (pinfunction "C_C") (pintype "passive"))
      (node (ref "R18") (pin "2") (pinfunction "2_2") (pintype "passive"))
    )
    (net (code "30") (name "Net-(LED10-PadA)") (class "Default")
      (node (ref "LED10") (pin "A") (pinfunction "A_A") (pintype "passive"))
      (node (ref "R30") (pin "1") (pinfunction "1_1") (pintype "passive"))
    )
    (net (code "31") (name "Net-(MAX7221-A)") (class "Default")
      (node (ref "MAX7221") (pin "SEG_A") (pinfunction "A_SEG_A") (pintype "bidirectional"))
      (node (ref "U$23") (pin "A") (pinfunction "A_A") (pintype "bidirectional"))
      (node (ref "U$24") (pin "A") (pinfunction "A_A") (pintype "bidirectional"))
      (node (ref "U$25") (pin "A") (pinfunction "A_A") (pintype "bidirectional"))
      (node (ref "U$26") (pin "A") (pinfunction "A_A") (pintype "bidirectional"))
    )
    (net (code "32") (name "Net-(MAX7221-B)") (class "Default")
      (node (ref "MAX7221") (pin "SEG_B") (pinfunction "B_SEG_B") (pintype "bidirectional"))
      (node (ref "U$23") (pin "B") (pinfunction "B_B") (pintype "bidirectional"))
      (node (ref "U$24") (pin "B") (pinfunction "B_B") (pintype "bidirectional"))
      (node (ref "U$25") (pin "B") (pinfunction "B_B") (pintype "bidirectional"))
      (node (ref "U$26") (pin "B") (pinfunction "B_B") (pintype "bidirectional"))
    )
    (net (code "33") (name "Net-(MAX7221-C)") (class "Default")
      (node (ref "MAX7221") (pin "SEG_C") (pinfunction "C_SEG_C") (pintype "bidirectional"))
      (node (ref "U$23") (pin "C") (pinfunction "C_C") (pintype "bidirectional"))
      (node (ref "U$24") (pin "C") (pinfunction "C_C") (pintype "bidirectional"))
      (node (ref "U$25") (pin "C") (pinfunction "C_C") (pintype "bidirectional"))
      (node (ref "U$26") (pin "C") (pinfunction "C_C") (pintype "bidirectional"))
    )
    (net (code "34") (name "Net-(MAX7221-D)") (class "Default")
      (node (ref "MAX7221") (pin "SEG_D") (pinfunction "D_SEG_D") (pintype "bidirectional"))
      (node (ref "U$23") (pin "D") (pinfunction "D_D") (pintype "bidirectional"))
      (node (ref "U$24") (pin "D") (pinfunction "D_D") (pintype "bidirectional"))
      (node (ref "U$25") (pin "D") (pinfunction "D_D") (pintype "bidirectional"))
      (node (ref "U$26") (pin "D") (pinfunction "D_D") (pintype "bidirectional"))
    )
    (net (code "35") (name "Net-(MAX7221-DP)") (class "Default")
      (node (ref "MAX7221") (pin "SEG_DP") (pinfunction "DP_SEG_DP") (pintype "bidirectional"))
      (node (ref "U$23") (pin "DP") (pinfunction "DOT_DP") (pintype "bidirectional"))
      (node (ref "U$24") (pin "DP") (pinfunction "DOT_DP") (pintype "bidirectional"))
      (node (ref "U$25") (pin "DP") (pinfunction "DOT_DP") (pintype "bidirectional"))
      (node (ref "U$26") (pin "DP") (pinfunction "DOT_DP") (pintype "bidirectional"))
    )
    (net (code "36") (name "Net-(MAX7221-E)") (class "Default")
      (node (ref "MAX7221") (pin "SEG_E") (pinfunction "E_SEG_E") (pintype "bidirectional"))
      (node (ref "U$23") (pin "E") (pinfunction "E_E") (pintype "bidirectional"))
      (node (ref "U$24") (pin "E") (pinfunction "E_E") (pintype "bidirectional"))
      (node (ref "U$25") (pin "E") (pinfunction "E_E") (pintype "bidirectional"))
      (node (ref "U$26") (pin "E") (pinfunction "E_E") (pintype "bidirectional"))
    )
    (net (code "37") (name "Net-(MAX7221-F)") (class "Default")
      (node (ref "MAX7221") (pin "SEG_F") (pinfunction "F_SEG_F") (pintype "bidirectional"))
      (node (ref "U$23") (pin "F") (pinfunction "F_F") (pintype "bidirectional"))
      (node (ref "U$24") (pin "F") (pinfunction "F_F") (pintype "bidirectional"))
      (node (ref "U$25") (pin "F") (pinfunction "F_F") (pintype "bidirectional"))
      (node (ref "U$26") (pin "F") (pinfunction "F_F") (pintype "bidirectional"))
    )
    (net (code "38") (name "Net-(MAX7221-G)") (class "Default")
      (node (ref "MAX7221") (pin "SEG_G") (pinfunction "G_SEG_G") (pintype "bidirectional"))
      (node (ref "U$23") (pin "G") (pinfunction "G_G") (pintype "bidirectional"))
      (node (ref "U$24") (pin "G") (pinfunction "G_G") (pintype "bidirectional"))
      (node (ref "U$25") (pin "G") (pinfunction "G_G") (pintype "bidirectional"))
      (node (ref "U$26") (pin "G") (pinfunction "G_G") (pintype "bidirectional"))
    )
    (net (code "39") (name "Net-(MAX7221-PadISET)") (class "Default")
      (node (ref "MAX7221") (pin "ISET") (pinfunction "ISET_ISET") (pintype "bidirectional"))
      (node (ref "R16") (pin "2") (pinfunction "2_2") (pintype "passive"))
    )
    (net (code "40") (name "Net-(PTC2-2)") (class "Default")
      (node (ref "PTC2") (pin "P$2") (pinfunction "2_P$2") (pintype "passive"))
      (node (ref "U$15") (pin "PWR2") (pinfunction "TIP_PWR2") (pintype "bidirectional"))
    )
    (net (code "41") (name "Net-(Q2-B)") (class "Default")
      (node (ref "Q2") (pin "1") (pinfunction "B_1") (pintype "passive"))
      (node (ref "R33") (pin "2") (pinfunction "2_2") (pintype "passive"))
      (node (ref "R34") (pin "2") (pinfunction "2_2") (pintype "passive"))
    )
    (net (code "42") (name "Net-(U$23-GN)") (class "Default")
      (node (ref "MAX7221") (pin "DIG0") (pinfunction "DIG0_DIG0") (pintype "bidirectional"))
      (node (ref "U$23") (pin "GND") (pinfunction "GN_GND") (pintype "bidirectional"))
      (node (ref "U$23") (pin "GND2") (pinfunction "GND_GND2") (pintype "bidirectional"))
    )
    (net (code "43") (name "Net-(U$24-GN)") (class "Default")
      (node (ref "MAX7221") (pin "DIG1") (pinfunction "DIG1_DIG1") (pintype "bidirectional"))
      (node (ref "U$24") (pin "GND") (pinfunction "GN_GND") (pintype "bidirectional"))
      (node (ref "U$24") (pin "GND2") (pinfunction "GND_GND2") (pintype "bidirectional"))
    )
    (net (code "44") (name "Net-(U$25-GN)") (class "Default")
      (node (ref "MAX7221") (pin "DIG2") (pinfunction "DIG2_DIG2") (pintype "bidirectional"))
      (node (ref "U$25") (pin "GND") (pinfunction "GN_GND") (pintype "bidirectional"))
      (node (ref "U$25") (pin "GND2") (pinfunction "GND_GND2") (pintype "bidirectional"))
    )
    (net (code "45") (name "Net-(U$26-GN)") (class "Default")
      (node (ref "MAX7221") (pin "DIG3") (pinfunction "DIG3_DIG3") (pintype "bidirectional"))
      (node (ref "U$26") (pin "GND") (pinfunction "GN_GND") (pintype "bidirectional"))
      (node (ref "U$26") (pin "GND2") (pinfunction "GND_GND2") (pintype "bidirectional"))
    )
    (net (code "46") (name "Net-(U2-B1)") (class "Default")
      (node (ref "MAX7221") (pin "DIN") (pinfunction "DIN_DIN") (pintype "bidirectional"))
      (node (ref "U2") (pin "20") (pinfunction "B1_20") (pintype "bidirectional"))
    )
    (net (code "47") (name "Net-(U2-B2)") (class "Default")
      (node (ref "MAX7221") (pin "CLK") (pinfunction "CLK_CLK") (pintype "bidirectional"))
      (node (ref "U2") (pin "18") (pinfunction "B2_18") (pintype "bidirectional"))
    )
    (net (code "48") (name "Net-(U2-B3)") (class "Default")
      (node (ref "MAX7221") (pin "LOAD") (pinfunction "LOAD_LOAD") (pintype "bidirectional"))
      (node (ref "U2") (pin "17") (pinfunction "B3_17") (pintype "bidirectional"))
    )
    (net (code "49") (name "Net-(U3-B1)") (class "Default")
      (node (ref "U$61") (pin "PIN1") (pinfunction "PIN1_PIN1") (pintype "bidirectional"))
      (node (ref "U3") (pin "20") (pinfunction "B1_20") (pintype "bidirectional"))
    )
    (net (code "50") (name "Net-(U3-B2)") (class "Default")
      (node (ref "U$61") (pin "PIN2") (pinfunction "PIN2_PIN2") (pintype "bidirectional"))
      (node (ref "U3") (pin "18") (pinfunction "B2_18") (pintype "bidirectional"))
    )
    (net (code "51") (name "Net-(U3-B3)") (class "Default")
      (node (ref "U$61") (pin "PIN3") (pinfunction "PIN3_PIN3") (pintype "bidirectional"))
      (node (ref "U3") (pin "17") (pinfunction "B3_17") (pintype "bidirectional"))
    )
    (net (code "52") (name "Net-(U3-B4)") (class "Default")
      (node (ref "U$61") (pin "PIN4") (pinfunction "PIN4_PIN4") (pintype "bidirectional"))
      (node (ref "U3") (pin "16") (pinfunction "B4_16") (pintype "bidirectional"))
    )
    (net (code "53") (name "Net-(U3-B5)") (class "Default")
      (node (ref "U$61") (pin "PIN5") (pinfunction "PIN5_PIN5") (pintype "bidirectional"))
      (node (ref "U3") (pin "15") (pinfunction "B5_15") (pintype "bidirectional"))
    )
    (net (code "54") (name "Net-(U3-B6)") (class "Default")
      (node (ref "U$61") (pin "PIN6") (pinfunction "PIN6_PIN6") (pintype "bidirectional"))
      (node (ref "U3") (pin "14") (pinfunction "B6_14") (pintype "bidirectional"))
    )
    (net (code "55") (name "Net-(XB1-ASSOC{slash}AD5{slash}DIO5)") (class "Default")
      (node (ref "LED9") (pin "A") (pinfunction "A_A") (pintype "passive"))
      (node (ref "XB1") (pin "15") (pinfunction "ASSOC/AD5/DIO5_15") (pintype "bidirectional"))
    )
    (net (code "56") (name "Net-(XB1-PWM0{slash}RSSI)") (class "Default")
      (node (ref "R17") (pin "1") (pinfunction "1_1") (pintype "passive"))
      (node (ref "XB1") (pin "6") (pinfunction "PWM0/RSSI_6") (pintype "output"))
    )
    (net (code "57") (name "PA0") (class "Default")
      (node (ref "U$1") (pin "P$75") (pinfunction "PA0_P$75") (pintype "bidirectional"))
    )
    (net (code "58") (name "PA1") (class "Default")
      (node (ref "U$1") (pin "P$76") (pinfunction "PA1_P$76") (pintype "bidirectional"))
    )
    (net (code "59") (name "PA2") (class "Default")
      (node (ref "U$1") (pin "P$77") (pinfunction "PA2_P$77") (pintype "bidirectional"))
    )
    (net (code "60") (name "PB4") (class "Default")
      (node (ref "U$1") (pin "P$54") (pinfunction "PB4_P$54") (pintype "bidirectional"))
    )
    (net (code "61") (name "PB9") (class "Default")
      (node (ref "U$1") (pin "P$59") (pinfunction "PB9_P$59") (pintype "bidirectional"))
    )
    (net (code "62") (name "PC0") (class "Default")
      (node (ref "U$1") (pin "P$71") (pinfunction "PC0_P$71") (pintype "bidirectional"))
    )
    (net (code "63") (name "PC1") (class "Default")
      (node (ref "U$1") (pin "P$72") (pinfunction "PC1_P$72") (pintype "bidirectional"))
    )
    (net (code "64") (name "PC2") (class "Default")
      (node (ref "U$1") (pin "P$73") (pinfunction "PC2_P$73") (pintype "bidirectional"))
    )
    (net (code "65") (name "PC3") (class "Default")
      (node (ref "U$1") (pin "P$74") (pinfunction "PC3_P$74") (pintype "bidirectional"))
    )
    (net (code "66") (name "PC13") (class "Default")
      (node (ref "U$1") (pin "P$68") (pinfunction "PC13_P$68") (pintype "bidirectional"))
    )
    (net (code "67") (name "PD4") (class "Default")
      (node (ref "U$1") (pin "P$50") (pinfunction "PD4_P$50") (pintype "bidirectional"))
    )
    (net (code "68") (name "PD7") (class "Default")
      (node (ref "U$1") (pin "P$53") (pinfunction "PD7_P$53") (pintype "bidirectional"))
    )
    (net (code "69") (name "PE0") (class "Default")
      (node (ref "U$1") (pin "P$60") (pinfunction "PE0_P$60") (pintype "bidirectional"))
    )
    (net (code "70") (name "PE1") (class "Default")
      (node (ref "U$1") (pin "P$61") (pinfunction "PE1_P$61") (pintype "bidirectional"))
    )
    (net (code "71") (name "PE2") (class "Default")
      (node (ref "U$1") (pin "P$63") (pinfunction "PE2_P$63") (pintype "bidirectional"))
    )
    (net (code "72") (name "PE3") (class "Default")
      (node (ref "U$1") (pin "P$64") (pinfunction "PE3_P$64") (pintype "bidirectional"))
    )
    (net (code "73") (name "PE4") (class "Default")
      (node (ref "U$1") (pin "P$65") (pinfunction "PE4_P$65") (pintype "bidirectional"))
    )
    (net (code "74") (name "PE5") (class "Default")
      (node (ref "U$1") (pin "P$66") (pinfunction "PE5_P$66") (pintype "bidirectional"))
    )
    (net (code "75") (name "PE6") (class "Default")
      (node (ref "U$1") (pin "P$67") (pinfunction "PE6_P$67") (pintype "bidirectional"))
    )
    (net (code "76") (name "RTS-XBEE") (class "Default")
      (node (ref "U$1") (pin "P$27") (pinfunction "PD8_P$27") (pintype "bidirectional"))
      (node (ref "XB1") (pin "16") (pinfunction "~{RTS}/AD6/DIO6_16") (pintype "bidirectional"))
    )
    (net (code "77") (name "SCL") (class "Default")
      (node (ref "U$1") (pin "P$58") (pinfunction "PB8_P$58") (pintype "bidirectional"))
    )
    (net (code "78") (name "SDA") (class "Default")
      (node (ref "U$1") (pin "P$57") (pinfunction "PB7_P$57") (pintype "bidirectional"))
    )
    (net (code "79") (name "SDIO_CK") (class "Default")
      (node (ref "U$1") (pin "P$47") (pinfunction "PC12_P$47") (pintype "bidirectional"))
      (node (ref "X3") (pin "5") (pinfunction "5_5") (pintype "passive"))
    )
    (net (code "80") (name "SDIO_CMD") (class "Default")
      (node (ref "R7") (pin "1") (pinfunction "1_1") (pintype "passive"))
      (node (ref "U$1") (pin "P$48") (pinfunction "PD2_P$48") (pintype "bidirectional"))
      (node (ref "X3") (pin "2") (pinfunction "2_2") (pintype "passive"))
    )
    (net (code "81") (name "SDIO_D0") (class "Default")
      (node (ref "R8") (pin "1") (pinfunction "1_1") (pintype "passive"))
      (node (ref "U$1") (pin "P$37") (pinfunction "PC8_P$37") (pintype "bidirectional"))
      (node (ref "X3") (pin "7") (pinfunction "7_7") (pintype "passive"))
    )
    (net (code "82") (name "SDIO_D1") (class "Default")
      (node (ref "R9") (pin "1") (pinfunction "1_1") (pintype "passive"))
      (node (ref "U$1") (pin "P$38") (pinfunction "PC9_P$38") (pintype "bidirectional"))
      (node (ref "X3") (pin "8") (pinfunction "8_8") (pintype "passive"))
    )
    (net (code "83") (name "SDIO_D2") (class "Default")
      (node (ref "R10") (pin "1") (pinfunction "1_1") (pintype "passive"))
      (node (ref "U$1") (pin "P$45") (pinfunction "PC10_P$45") (pintype "bidirectional"))
      (node (ref "X3") (pin "9") (pinfunction "9_9") (pintype "passive"))
    )
    (net (code "84") (name "SDIO_D3") (class "Default")
      (node (ref "R6") (pin "1") (pinfunction "1_1") (pintype "passive"))
      (node (ref "U$1") (pin "P$46") (pinfunction "PC11_P$46") (pintype "bidirectional"))
      (node (ref "X3") (pin "1") (pinfunction "1_1") (pintype "passive"))
    )
    (net (code "85") (name "SD_IN") (class "Default")
      (node (ref "U$1") (pin "P$49") (pinfunction "PD3_P$49") (pintype "bidirectional"))
      (node (ref "X3") (pin "SW1") (pinfunction "SW1_SW1") (pintype "passive"))
    )
    (net (code "86") (name "SPI_LOAD") (class "Default")
      (node (ref "U$1") (pin "P$40") (pinfunction "PA9_P$40") (pintype "bidirectional"))
      (node (ref "U2") (pin "4") (pinfunction "A3_4") (pintype "bidirectional"))
    )
    (net (code "87") (name "SPI_MISO") (class "Default")
      (node (ref "U$1") (pin "P$25") (pinfunction "PB14_P$25") (pintype "bidirectional"))
    )
    (net (code "88") (name "SPI_MOSI") (class "Default")
      (node (ref "U$1") (pin "P$26") (pinfunction "PB15_P$26") (pintype "bidirectional"))
      (node (ref "U2") (pin "1") (pinfunction "A1_1") (pintype "bidirectional"))
    )
    (net (code "89") (name "SPI_SCK") (class "Default")
      (node (ref "U$1") (pin "P$24") (pinfunction "PB13_P$24") (pintype "bidirectional"))
      (node (ref "U2") (pin "3") (pinfunction "A2_3") (pintype "bidirectional"))
    )
    (net (code "90") (name "SS-XBEE") (class "Default")
      (node (ref "C2") (pin "2") (pinfunction "P$2_2") (pintype "passive"))
      (node (ref "R17") (pin "2") (pinfunction "2_2") (pintype "passive"))
    )
    (net (code "91") (name "SW1") (class "Default")
      (node (ref "R2") (pin "1") (pinfunction "1_1") (pintype "passive"))
      (node (ref "S5") (pin "S") (pinfunction "S_S") (pintype "passive"))
      (node (ref "U$1") (pin "P$11") (pinfunction "PE8_P$11") (pintype "bidirectional"))
    )
    (net (code "92") (name "SW2") (class "Default")
      (node (ref "R3") (pin "1") (pinfunction "1_1") (pintype "passive"))
      (node (ref "S6") (pin "S") (pinfunction "S_S") (pintype "passive"))
      (node (ref "U$1") (pin "P$12") (pinfunction "PE9_P$12") (pintype "bidirectional"))
    )
    (net (code "93") (name "SW3") (class "Default")
      (node (ref "R4") (pin "1") (pinfunction "1_1") (pintype "passive"))
      (node (ref "S7") (pin "S") (pinfunction "S_S") (pintype "passive"))
      (node (ref "U$1") (pin "P$13") (pinfunction "PE10_P$13") (pintype "bidirectional"))
    )
    (net (code "94") (name "SW4") (class "Default")
      (node (ref "R5") (pin "1") (pinfunction "1_1") (pintype "passive"))
      (node (ref "S8") (pin "S") (pinfunction "S_S") (pintype "passive"))
      (node (ref "U$1") (pin "P$14") (pinfunction "PE11_P$14") (pintype "bidirectional"))
    )
    (net (code "95") (name "SW5") (class "Default")
      (node (ref "R11") (pin "1") (pinfunction "1_1") (pintype "passive"))
      (node (ref "S1") (pin "1") (pinfunction "S_1") (pintype "passive"))
      (node (ref "S1") (pin "2") (pinfunction "S1_2") (pintype "passive"))
      (node (ref "U$1") (pin "P$15") (pinfunction "PE12_P$15") (pintype "bidirectional"))
    )
    (net (code "96") (name "SW6") (class "Default")
      (node (ref "R12") (pin "1") (pinfunction "1_1") (pintype "passive"))
      (node (ref "S2") (pin "1") (pinfunction "S_1") (pintype "passive"))
      (node (ref "S2") (pin "2") (pinfunction "S1_2") (pintype "passive"))
      (node (ref "U$1") (pin "P$16") (pinfunction "PE13_P$16") (pintype "bidirectional"))
    )
    (net (code "97") (name "SW7") (class "Default")
      (node (ref "R13") (pin "1") (pinfunction "1_1") (pintype "passive"))
      (node (ref "S3") (pin "1") (pinfunction "S_1") (pintype "passive"))
      (node (ref "S3") (pin "2") (pinfunction "S1_2") (pintype "passive"))
      (node (ref "U$1") (pin "P$17") (pinfunction "PE14_P$17") (pintype "bidirectional"))
    )
    (net (code "98") (name "SW8") (class "Default")
      (node (ref "R14") (pin "1") (pinfunction "1_1") (pintype "passive"))
      (node (ref "S4") (pin "1") (pinfunction "S_1") (pintype "passive"))
      (node (ref "S4") (pin "2") (pinfunction "S1_2") (pintype "passive"))
      (node (ref "U$1") (pin "P$18") (pinfunction "PE15_P$18") (pintype "bidirectional"))
    )
    (net (code "99") (name "USART1_RX") (class "Default")
      (node (ref "U$1") (pin "P$22") (pinfunction "PB11_P$22") (pintype "bidirectional"))
      (node (ref "U$2") (pin "P$17") (pinfunction "TX_P$17") (pintype "bidirectional"))
      (node (ref "XB1") (pin "2") (pinfunction "DOUT_2") (pintype "output"))
    )
    (net (code "100") (name "USART1_TX") (class "Default")
      (node (ref "U$1") (pin "P$21") (pinfunction "PB10_P$21") (pintype "bidirectional"))
      (node (ref "U$2") (pin "P$18") (pinfunction "RX_P$18") (pintype "bidirectional"))
      (node (ref "XB1") (pin "3") (pinfunction "DIN/~{CONFIG}_3") (pintype "input"))
    )
    (net (code "101") (name "USART2_RX") (class "Default")
      (node (ref "U$1") (pin "P$52") (pinfunction "PD6_P$52") (pintype "bidirectional"))
    )
    (net (code "102") (name "USART2_TX") (class "Default")
      (node (ref "U$1") (pin "P$51") (pinfunction "PD5_P$51") (pintype "bidirectional"))
    )
    (net (code "103") (name "V-SENSE") (class "Default")
      (node (ref "Q2") (pin "2") (pinfunction "E_2") (pintype "passive"))
      (node (ref "U$1") (pin "P$39") (pinfunction "PA8_P$39") (pintype "bidirectional"))
    )
    (net (code "104") (name "unconnected-(MAX7221-PadDIG4)") (class "Default")
      (node (ref "MAX7221") (pin "DIG4") (pinfunction "DIG4_DIG4") (pintype "bidirectional"))
    )
    (net (code "105") (name "unconnected-(MAX7221-PadDIG5)") (class "Default")
      (node (ref "MAX7221") (pin "DIG5") (pinfunction "DIG5_DIG5") (pintype "bidirectional"))
    )
    (net (code "106") (name "unconnected-(MAX7221-PadDIG6)") (class "Default")
      (node (ref "MAX7221") (pin "DIG6") (pinfunction "DIG6_DIG6") (pintype "bidirectional"))
    )
    (net (code "107") (name "unconnected-(MAX7221-PadDIG7)") (class "Default")
      (node (ref "MAX7221") (pin "DIG7") (pinfunction "DIG7_DIG7") (pintype "bidirectional"))
    )
    (net (code "108") (name "unconnected-(MAX7221-PadDOUT)") (class "Default")
      (node (ref "MAX7221") (pin "DOUT") (pinfunction "DOUT_DOUT") (pintype "bidirectional"))
    )
    (net (code "109") (name "unconnected-(RV1-S-PadP$2)") (class "Default")
      (node (ref "RV1") (pin "P$2") (pinfunction "S_P$2") (pintype "passive"))
    )
    (net (code "110") (name "unconnected-(RV2-S-PadP$2)") (class "Default")
      (node (ref "RV2") (pin "P$2") (pinfunction "S_P$2") (pintype "passive"))
    )
    (net (code "111") (name "unconnected-(RV3-S-PadP$2)") (class "Default")
      (node (ref "RV3") (pin "P$2") (pinfunction "S_P$2") (pintype "passive"))
    )
    (net (code "112") (name "unconnected-(RV4-S-PadP$2)") (class "Default")
      (node (ref "RV4") (pin "P$2") (pinfunction "S_P$2") (pintype "passive"))
    )
    (net (code "113") (name "unconnected-(S5-PadO)") (class "Default")
      (node (ref "S5") (pin "O") (pinfunction "O_O") (pintype "passive"))
    )
    (net (code "114") (name "unconnected-(S6-PadO)") (class "Default")
      (node (ref "S6") (pin "O") (pinfunction "O_O") (pintype "passive"))
    )
    (net (code "115") (name "unconnected-(S7-PadO)") (class "Default")
      (node (ref "S7") (pin "O") (pinfunction "O_O") (pintype "passive"))
    )
    (net (code "116") (name "unconnected-(S8-PadO)") (class "Default")
      (node (ref "S8") (pin "O") (pinfunction "O_O") (pintype "passive"))
    )
    (net (code "117") (name "unconnected-(U$1A-PA3-PadP$1)") (class "Default")
      (node (ref "U$1") (pin "P$1") (pinfunction "PA3_P$1") (pintype "bidirectional"))
    )
    (net (code "118") (name "unconnected-(U$1A-PA4-PadP$2)") (class "Default")
      (node (ref "U$1") (pin "P$2") (pinfunction "PA4_P$2") (pintype "bidirectional"))
    )
    (net (code "119") (name "unconnected-(U$1B-PB12-PadP$23)") (class "Default")
      (node (ref "U$1") (pin "P$23") (pinfunction "PB12_P$23") (pintype "bidirectional"))
    )
    (net (code "120") (name "unconnected-(U$1B-PC6-PadP$35)") (class "Default")
      (node (ref "U$1") (pin "P$35") (pinfunction "PC6_P$35") (pintype "bidirectional"))
    )
    (net (code "121") (name "unconnected-(U$1B-PC7-PadP$36)") (class "Default")
      (node (ref "U$1") (pin "P$36") (pinfunction "PC7_P$36") (pintype "bidirectional"))
    )
    (net (code "122") (name "unconnected-(U$1B-PD10-PadP$29)") (class "Default")
      (node (ref "U$1") (pin "P$29") (pinfunction "PD10_P$29") (pintype "bidirectional"))
    )
    (net (code "123") (name "unconnected-(U$1B-PD11-PadP$30)") (class "Default")
      (node (ref "U$1") (pin "P$30") (pinfunction "PD11_P$30") (pintype "bidirectional"))
    )
    (net (code "124") (name "unconnected-(U$1B-PD12-PadP$31)") (class "Default")
      (node (ref "U$1") (pin "P$31") (pinfunction "PD12_P$31") (pintype "bidirectional"))
    )
    (net (code "125") (name "unconnected-(U$1B-PD13-PadP$32)") (class "Default")
      (node (ref "U$1") (pin "P$32") (pinfunction "PD13_P$32") (pintype "bidirectional"))
    )
    (net (code "126") (name "unconnected-(U$1B-PD14-PadP$33)") (class "Default")
      (node (ref "U$1") (pin "P$33") (pinfunction "PD14_P$33") (pintype "bidirectional"))
    )
    (net (code "127") (name "unconnected-(U$1B-PD15-PadP$34)") (class "Default")
      (node (ref "U$1") (pin "P$34") (pinfunction "PD15_P$34") (pintype "bidirectional"))
    )
    (net (code "128") (name "unconnected-(U$2-LRNLED-PadP$6)") (class "Default")
      (node (ref "U$2") (pin "P$6") (pinfunction "LRNLED_P$6") (pintype "bidirectional"))
    )
    (net (code "129") (name "unconnected-(U$2-LRNSW-PadP$5)") (class "Default")
      (node (ref "U$2") (pin "P$5") (pinfunction "LRNSW_P$5") (pintype "bidirectional"))
    )
    (net (code "130") (name "unconnected-(U$2-OP1-PadP$3)") (class "Default")
      (node (ref "U$2") (pin "P$3") (pinfunction "OP1_P$3") (pintype "bidirectional"))
    )
    (net (code "131") (name "unconnected-(U$2-OP2-PadP$4)") (class "Default")
      (node (ref "U$2") (pin "P$4") (pinfunction "OP2_P$4") (pintype "bidirectional"))
    )
    (net (code "132") (name "unconnected-(U$2-OP3-PadP$7)") (class "Default")
      (node (ref "U$2") (pin "P$7") (pinfunction "OP3_P$7") (pintype "bidirectional"))
    )
    (net (code "133") (name "unconnected-(U$2-OP4-PadP$8)") (class "Default")
      (node (ref "U$2") (pin "P$8") (pinfunction "OP4_P$8") (pintype "bidirectional"))
    )
    (net (code "134") (name "unconnected-(U$2-OP5-PadP$9)") (class "Default")
      (node (ref "U$2") (pin "P$9") (pinfunction "OP5_P$9") (pintype "bidirectional"))
    )
    (net (code "135") (name "unconnected-(U$2-OP6-PadP$11)") (class "Default")
      (node (ref "U$2") (pin "P$11") (pinfunction "OP6_P$11") (pintype "bidirectional"))
    )
    (net (code "136") (name "unconnected-(U$2-OP7-PadP$12)") (class "Default")
      (node (ref "U$2") (pin "P$12") (pinfunction "OP7_P$12") (pintype "bidirectional"))
    )
    (net (code "137") (name "unconnected-(U$2-OP8-PadP$13)") (class "Default")
      (node (ref "U$2") (pin "P$13") (pinfunction "OP8_P$13") (pintype "bidirectional"))
    )
    (net (code "138") (name "unconnected-(U$2-OPT1-PadP$10)") (class "Default")
      (node (ref "U$2") (pin "P$10") (pinfunction "OPT1_P$10") (pintype "bidirectional"))
    )
    (net (code "139") (name "unconnected-(U$61-PadPIN8)") (class "Default")
      (node (ref "U$61") (pin "PIN8") (pinfunction "PIN8_PIN8") (pintype "bidirectional"))
    )
    (net (code "140") (name "unconnected-(U$61-PadPIN9)") (class "Default")
      (node (ref "U$61") (pin "PIN9") (pinfunction "PIN9_PIN9") (pintype "bidirectional"))
    )
    (net (code "141") (name "unconnected-(U$61-PadPIN10)") (class "Default")
      (node (ref "U$61") (pin "PIN10") (pinfunction "PIN10_PIN10") (pintype "bidirectional"))
    )
    (net (code "142") (name "unconnected-(U$61-PadPIN11)") (class "Default")
      (node (ref "U$61") (pin "PIN11") (pinfunction "PIN11_PIN11") (pintype "bidirectional"))
    )
    (net (code "143") (name "unconnected-(U$61-PadPIN12)") (class "Default")
      (node (ref "U$61") (pin "PIN12") (pinfunction "PIN12_PIN12") (pintype "bidirectional"))
    )
    (net (code "144") (name "unconnected-(U$61-PadPIN13)") (class "Default")
      (node (ref "U$61") (pin "PIN13") (pinfunction "PIN13_PIN13") (pintype "bidirectional"))
    )
    (net (code "145") (name "unconnected-(U$61-PadPIN14)") (class "Default")
      (node (ref "U$61") (pin "PIN14") (pinfunction "PIN14_PIN14") (pintype "bidirectional"))
    )
    (net (code "146") (name "unconnected-(U$67-PadPIN1)") (class "Default")
      (node (ref "U$67") (pin "PIN1") (pinfunction "PIN1_PIN1") (pintype "bidirectional"))
    )
    (net (code "147") (name "unconnected-(U$67-PadPIN2)") (class "Default")
      (node (ref "U$67") (pin "PIN2") (pinfunction "PIN2_PIN2") (pintype "bidirectional"))
    )
    (net (code "148") (name "unconnected-(U$67-PadPIN3)") (class "Default")
      (node (ref "U$67") (pin "PIN3") (pinfunction "PIN3_PIN3") (pintype "bidirectional"))
    )
    (net (code "149") (name "unconnected-(U$67-PadPIN4)") (class "Default")
      (node (ref "U$67") (pin "PIN4") (pinfunction "PIN4_PIN4") (pintype "bidirectional"))
    )
    (net (code "150") (name "unconnected-(U$68-PadPIN1)") (class "Default")
      (node (ref "U$68") (pin "PIN1") (pinfunction "PIN1_PIN1") (pintype "bidirectional"))
    )
    (net (code "151") (name "unconnected-(U$68-PadPIN2)") (class "Default")
      (node (ref "U$68") (pin "PIN2") (pinfunction "PIN2_PIN2") (pintype "bidirectional"))
    )
    (net (code "152") (name "unconnected-(U$68-PadPIN3)") (class "Default")
      (node (ref "U$68") (pin "PIN3") (pinfunction "PIN3_PIN3") (pintype "bidirectional"))
    )
    (net (code "153") (name "unconnected-(U$68-PadPIN4)") (class "Default")
      (node (ref "U$68") (pin "PIN4") (pinfunction "PIN4_PIN4") (pintype "bidirectional"))
    )
    (net (code "154") (name "unconnected-(U$68-PadPIN5)") (class "Default")
      (node (ref "U$68") (pin "PIN5") (pinfunction "PIN5_PIN5") (pintype "bidirectional"))
    )
    (net (code "155") (name "unconnected-(U$68-PadPIN6)") (class "Default")
      (node (ref "U$68") (pin "PIN6") (pinfunction "PIN6_PIN6") (pintype "bidirectional"))
    )
    (net (code "156") (name "unconnected-(U2-A4-Pad5)") (class "Default")
      (node (ref "U2") (pin "5") (pinfunction "A4_5") (pintype "bidirectional"))
    )
    (net (code "157") (name "unconnected-(U2-A5-Pad6)") (class "Default")
      (node (ref "U2") (pin "6") (pinfunction "A5_6") (pintype "bidirectional"))
    )
    (net (code "158") (name "unconnected-(U2-A6-Pad7)") (class "Default")
      (node (ref "U2") (pin "7") (pinfunction "A6_7") (pintype "bidirectional"))
    )
    (net (code "159") (name "unconnected-(U2-A7-Pad8)") (class "Default")
      (node (ref "U2") (pin "8") (pinfunction "A7_8") (pintype "bidirectional"))
    )
    (net (code "160") (name "unconnected-(U2-A8-Pad9)") (class "Default")
      (node (ref "U2") (pin "9") (pinfunction "A8_9") (pintype "bidirectional"))
    )
    (net (code "161") (name "unconnected-(U2-B4-Pad16)") (class "Default")
      (node (ref "U2") (pin "16") (pinfunction "B4_16") (pintype "bidirectional"))
    )
    (net (code "162") (name "unconnected-(U2-B5-Pad15)") (class "Default")
      (node (ref "U2") (pin "15") (pinfunction "B5_15") (pintype "bidirectional"))
    )
    (net (code "163") (name "unconnected-(U2-B6-Pad14)") (class "Default")
      (node (ref "U2") (pin "14") (pinfunction "B6_14") (pintype "bidirectional"))
    )
    (net (code "164") (name "unconnected-(U2-B7-Pad13)") (class "Default")
      (node (ref "U2") (pin "13") (pinfunction "B7_13") (pintype "bidirectional"))
    )
    (net (code "165") (name "unconnected-(U2-B8-Pad12)") (class "Default")
      (node (ref "U2") (pin "12") (pinfunction "B8_12") (pintype "bidirectional"))
    )
    (net (code "166") (name "unconnected-(U3-A1-Pad1)") (class "Default")
      (node (ref "U3") (pin "1") (pinfunction "A1_1") (pintype "bidirectional"))
    )
    (net (code "167") (name "unconnected-(U3-A2-Pad3)") (class "Default")
      (node (ref "U3") (pin "3") (pinfunction "A2_3") (pintype "bidirectional"))
    )
    (net (code "168") (name "unconnected-(U3-A3-Pad4)") (class "Default")
      (node (ref "U3") (pin "4") (pinfunction "A3_4") (pintype "bidirectional"))
    )
    (net (code "169") (name "unconnected-(U3-A4-Pad5)") (class "Default")
      (node (ref "U3") (pin "5") (pinfunction "A4_5") (pintype "bidirectional"))
    )
    (net (code "170") (name "unconnected-(U3-A5-Pad6)") (class "Default")
      (node (ref "U3") (pin "6") (pinfunction "A5_6") (pintype "bidirectional"))
    )
    (net (code "171") (name "unconnected-(U3-A6-Pad7)") (class "Default")
      (node (ref "U3") (pin "7") (pinfunction "A6_7") (pintype "bidirectional"))
    )
    (net (code "172") (name "unconnected-(U3-A7-Pad8)") (class "Default")
      (node (ref "U3") (pin "8") (pinfunction "A7_8") (pintype "bidirectional"))
    )
    (net (code "173") (name "unconnected-(U3-A8-Pad9)") (class "Default")
      (node (ref "U3") (pin "9") (pinfunction "A8_9") (pintype "bidirectional"))
    )
    (net (code "174") (name "unconnected-(U3-B7-Pad13)") (class "Default")
      (node (ref "U3") (pin "13") (pinfunction "B7_13") (pintype "bidirectional"))
    )
    (net (code "175") (name "unconnected-(U3-B8-Pad12)") (class "Default")
      (node (ref "U3") (pin "12") (pinfunction "B8_12") (pintype "bidirectional"))
    )
    (net (code "176") (name "unconnected-(X3-PadSW2)") (class "Default")
      (node (ref "X3") (pin "SW2") (pinfunction "SW2_SW2") (pintype "passive"))
    )
    (net (code "177") (name "unconnected-(XB1-AD0{slash}DIO0-Pad20)") (class "Default")
      (node (ref "XB1") (pin "20") (pinfunction "AD0/DIO0_20") (pintype "bidirectional"))
    )
    (net (code "178") (name "unconnected-(XB1-AD1{slash}DIO1-Pad19)") (class "Default")
      (node (ref "XB1") (pin "19") (pinfunction "AD1/DIO1_19") (pintype "bidirectional"))
    )
    (net (code "179") (name "unconnected-(XB1-AD2{slash}DIO2-Pad18)") (class "Default")
      (node (ref "XB1") (pin "18") (pinfunction "AD2/DIO2_18") (pintype "bidirectional"))
    )
    (net (code "180") (name "unconnected-(XB1-CD{slash}DOUT_EN{slash}DO8-Pad4)") (class "Default")
      (node (ref "XB1") (pin "4") (pinfunction "CD/DOUT_EN/DO8_4") (pintype "output"))
    )
    (net (code "181") (name "unconnected-(XB1-COORD_SEL{slash}AD3{slash}DIO3-Pad17)") (class "Default")
      (node (ref "XB1") (pin "17") (pinfunction "COORD_SEL/AD3/DIO3_17") (pintype "bidirectional"))
    )
    (net (code "182") (name "unconnected-(XB1-ON{slash}~{SLEEP}-Pad13)") (class "Default")
      (node (ref "XB1") (pin "13") (pinfunction "ON/~{SLEEP}_13") (pintype "output"))
    )
    (net (code "183") (name "unconnected-(XB1-RF_TX{slash}AD4{slash}DIO4-Pad11)") (class "Default")
      (node (ref "XB1") (pin "11") (pinfunction "RF_TX/AD4/DIO4_11") (pintype "bidirectional"))
    )
    (net (code "184") (name "unconnected-(XB1-VREF-Pad14)") (class "Default")
      (node (ref "XB1") (pin "14") (pinfunction "VREF_14") (pintype "input"))
    )
    (net (code "185") (name "unconnected-(XB1-~{DTR}{slash}SLEEP_RQ{slash}DI8-Pad9)") (class "Default")
      (node (ref "XB1") (pin "9") (pinfunction "~{DTR}/SLEEP_RQ/DI8_9") (pintype "bidirectional"))
    )
  )
)
